# OpenPLCv0_2_0_IOLED.net
KiCad netlist of a schematic drawn in Altium Designer
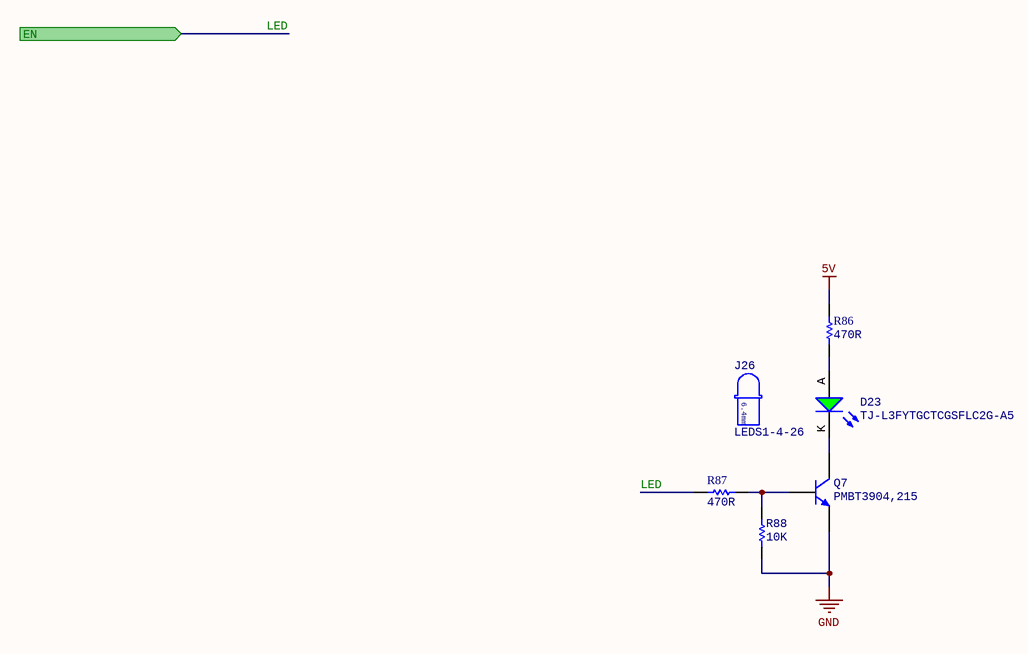
[diagram p0: OpenPLCv0.2.0_IOLED.SchDoc]

(export (version "E")
  (design (tool "Eeschema 10.0.6"))
  (components
    (comp (ref "D23")
      (value "TJ-L3FYTGCTCGSFLC2G-A5")
      (footprint "LED_3MM_SPACED_6.4MM_GREEN")
      (description "LED 3mm Green 515nm~530nm 1.8V~3.6V Through Hole Light Emitting Diodes (LED) RoHS C330751")
      (libsource (lib "BrauV2_Diode") (part "TJ-L3FYTGCTCGSFLC2G-A5"))
    )
    (comp (ref "J26")
      (value "LEDS1-4-26")
      (footprint "3MM_LED_SPACER_6.4MM")
      (description "3mm LED spacer 6.4mm height")
      (libsource (lib "BrauV2_Misc") (part "LEDS1-4-26"))
    )
    (comp (ref "Q7")
      (value "PMBT3904,215")
      (footprint "SOT23-3")
      (description "NPN 200mA 40V 250mW SOT-23(SOT-23-3) Transistors (NPN/PNP) RoHS")
      (libsource (lib "BrauV2_Transistor") (part "PMBT3904,215"))
    )
    (comp (ref "R86")
      (value "RC0402FR-07470RL")
      (footprint "SMD_RES_0402(1005)_N")
      (description "470Ω ±1% 1/16W ±100ppm/℃ 0402 Chip Resistor - Surface Mount RoHS")
      (fields (field (name "TOLERANCE") "1%") (field (name "RESISTANCE") "470R"))
      (libsource (lib "BrauV2_Resistor") (part "470R 0402 1% 1W"))
    )
    (comp (ref "R87")
      (value "RC0402FR-07470RL")
      (footprint "SMD_RES_0402(1005)_N")
      (description "470Ω ±1% 1/16W ±100ppm/℃ 0402 Chip Resistor - Surface Mount RoHS")
      (fields (field (name "TOLERANCE") "1%") (field (name "RESISTANCE") "470R"))
      (libsource (lib "BrauV2_Resistor") (part "470R 0402 1% 1W"))
    )
    (comp (ref "R88")
      (value "RC0402FR-0710KL")
      (footprint "SMD_RES_0402(1005)_N")
      (description "10kΩ ±1% 1/16W ±100ppm/℃ 0402 Chip Resistor - Surface Mount RoHS")
      (fields (field (name "TOLERANCE") "1%") (field (name "RESISTANCE") "10K"))
      (libsource (lib "BrauV2_Resistor") (part "10K 0402 1% 1/16W"))
    )
  )
  (nets
    (net (code "1") (name "/LED") (class "Default")
      (node (ref "R87") (pin "2") (pinfunction "2_2") (pintype "passive"))
    )
    (net (code "2") (name "5V") (class "Default")
      (node (ref "R86") (pin "2") (pinfunction "2_2") (pintype "passive"))
    )
    (net (code "3") (name "GND") (class "Default")
      (node (ref "Q7") (pin "2") (pinfunction "E_2") (pintype "passive"))
      (node (ref "R88") (pin "1") (pinfunction "1_1") (pintype "passive"))
    )
    (net (code "4") (name "Net-(D23-PadA)") (class "Default")
      (node (ref "D23") (pin "A") (pinfunction "A_A") (pintype "passive"))
      (node (ref "R86") (pin "1") (pinfunction "1_1") (pintype "passive"))
    )
    (net (code "5") (name "Net-(Q7-B)") (class "Default")
      (node (ref "Q7") (pin "1") (pinfunction "B_1") (pintype "passive"))
      (node (ref "R87") (pin "1") (pinfunction "1_1") (pintype "passive"))
      (node (ref "R88") (pin "2") (pinfunction "2_2") (pintype "passive"))
    )
    (net (code "6") (name "Net-(Q7-C)") (class "Default")
      (node (ref "D23") (pin "K") (pinfunction "K_K") (pintype "passive"))
      (node (ref "Q7") (pin "3") (pinfunction "C_3") (pintype "passive"))
    )
  )
)
